# 03-multimodal-battery-charger.net
KiCad netlist of a schematic drawn in Altium Designer
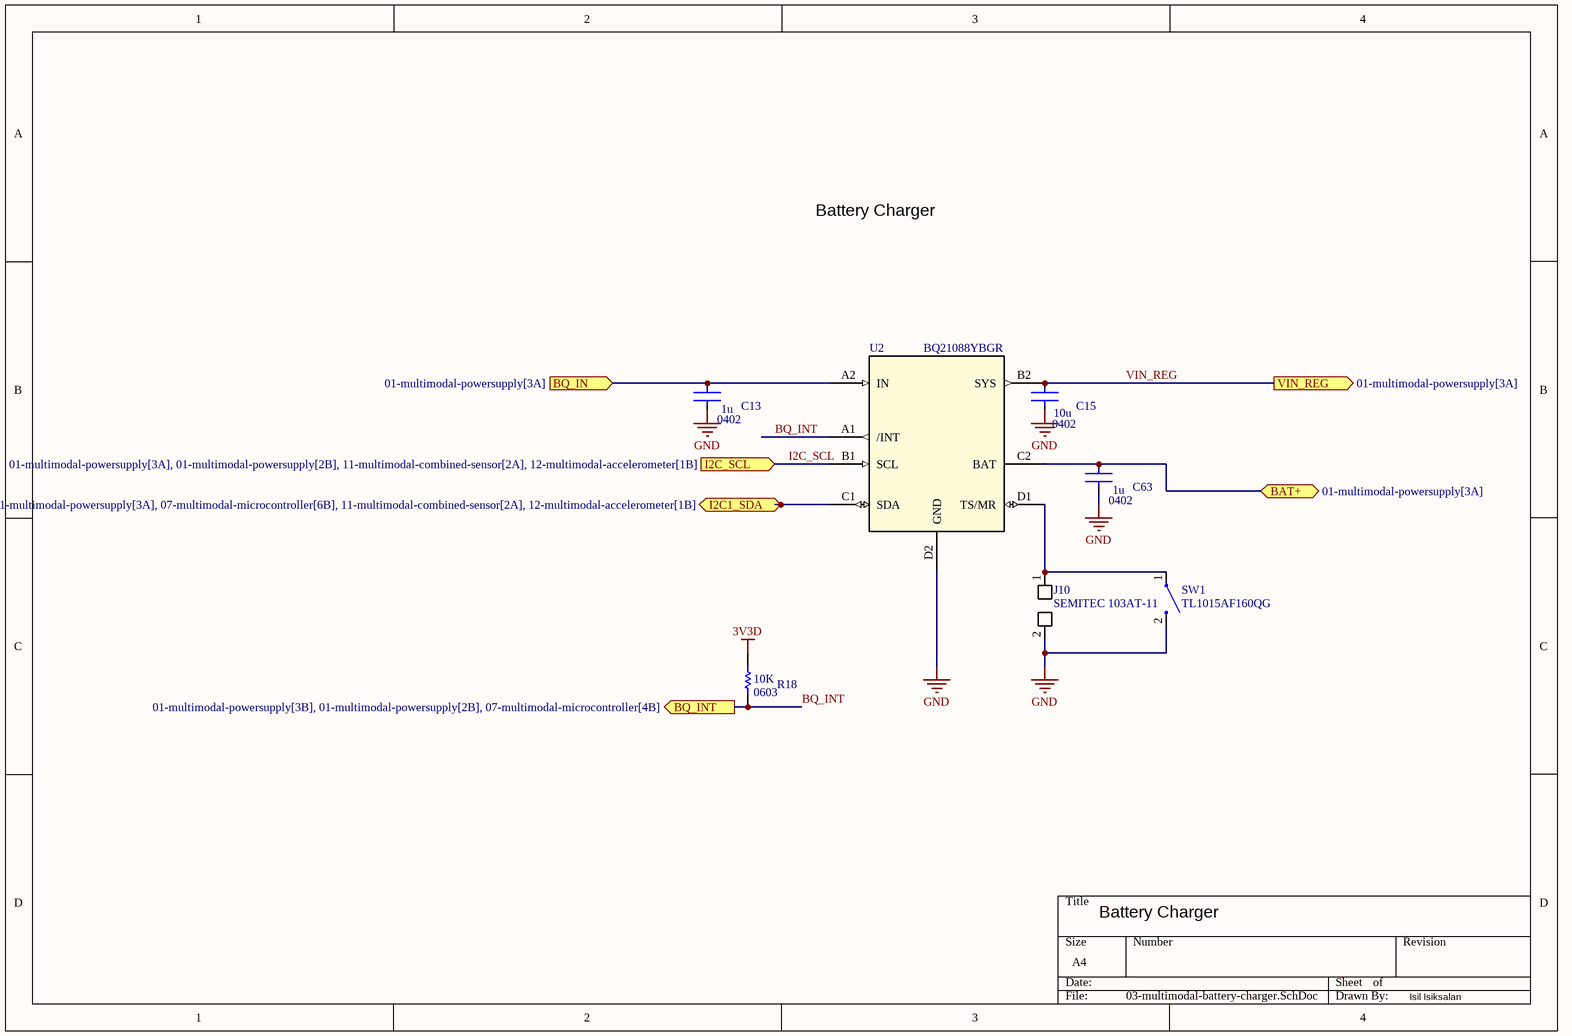
[diagram p0: 03-multimodal-battery-charger.SchDoc]

(export (version "E")
  (design (tool "Eeschema 10.0.6"))
  (components
    (comp (ref "C13")
      (value "C1005X5R1V105K050BC")
      (footprint "CAPTDK0402")
      (description "CAP CER 1UF 35V X5R 0402")
      (libsource (lib "multimodal") (part "C1005X5R1V105K050BC"))
    )
    (comp (ref "C15")
      (value "GRM155R61A106ME11D")
      (footprint "CAPTDK0402")
      (description "CAP CER 10UF 10V X5R 0402")
      (libsource (lib "multimodal") (part "GRM155R61A106ME11D"))
    )
    (comp (ref "C63")
      (value "C1005X5R1V105K050BC")
      (footprint "CAPTDK0402")
      (description "CAP CER 1UF 35V X5R 0402")
      (libsource (lib "multimodal") (part "C1005X5R1V105K050BC"))
    )
    (comp (ref "J10")
      (value "SEMITEC 103AT-11")
      (footprint "NTC_connection")
      (description "NTC THERMISTOR 10KOHM 1%")
      (libsource (lib "multimodal") (part "SEMITEC 103AT-11"))
    )
    (comp (ref "R18")
      (value "RMCF0603JG10K0")
      (footprint "RES-STACK-POLE-0603")
      (description "RES 10K OHM 5% 1/10W 0603")
      (libsource (lib "multimodal") (part "RMCF0603JG10K0"))
    )
    (comp (ref "SW1")
      (value "TL1015AF160QG")
      (footprint "TACTILE-SWITCH")
      (description "SWITCH TACTILE SPST-NO 0.05A 12V")
      (libsource (lib "multimodal") (part "TL1015AF160QG"))
    )
    (comp (ref "U2")
      (value "BQ21088YBGR")
      (footprint "YBG0008_TEX")
      (fields (field (name "COPYRIGHT") "Copyright (C) 2026 Ultra Librarian. All rights reserved."))
      (libsource (lib "multimodal") (part "BQ21088YBGR"))
    )
  )
  (nets
    (net (code "1") (name "/BAT+") (class "Default")
      (node (ref "C63") (pin "1") (pinfunction "1_1") (pintype "passive"))
      (node (ref "U2") (pin "C2") (pinfunction "BAT_C2") (pintype "passive"))
    )
    (net (code "2") (name "/BQ_IN") (class "Default")
      (node (ref "C13") (pin "1") (pinfunction "1_1") (pintype "passive"))
      (node (ref "U2") (pin "A2") (pinfunction "IN_A2") (pintype "input"))
    )
    (net (code "3") (name "/BQ_INT") (class "Default")
      (node (ref "R18") (pin "1") (pinfunction "1_1") (pintype "passive"))
      (node (ref "U2") (pin "A1") (pinfunction "/INT_A1") (pintype "output"))
    )
    (net (code "4") (name "/I2C1_SDA") (class "Default")
      (node (ref "U2") (pin "C1") (pinfunction "SDA_C1") (pintype "bidirectional"))
    )
    (net (code "5") (name "/I2C_SCL") (class "Default")
      (node (ref "U2") (pin "B1") (pinfunction "SCL_B1") (pintype "input"))
    )
    (net (code "6") (name "/VIN_REG") (class "Default")
      (node (ref "C15") (pin "1") (pinfunction "1_1") (pintype "passive"))
      (node (ref "U2") (pin "B2") (pinfunction "SYS_B2") (pintype "output"))
    )
    (net (code "7") (name "3V3D") (class "Default")
      (node (ref "R18") (pin "2") (pinfunction "2_2") (pintype "passive"))
    )
    (net (code "8") (name "GND") (class "Default")
      (node (ref "C13") (pin "2") (pinfunction "2_2") (pintype "passive"))
      (node (ref "C15") (pin "2") (pinfunction "2_2") (pintype "passive"))
      (node (ref "C63") (pin "2") (pinfunction "2_2") (pintype "passive"))
      (node (ref "J10") (pin "2") (pinfunction "2_2") (pintype "passive"))
      (node (ref "SW1") (pin "2") (pinfunction "2_2") (pintype "passive"))
      (node (ref "U2") (pin "D2") (pinfunction "GND_D2") (pintype "power_in"))
    )
    (net (code "9") (name "Net-(U2-TS{slash}MR)") (class "Default")
      (node (ref "J10") (pin "1") (pinfunction "1_1") (pintype "passive"))
      (node (ref "SW1") (pin "1") (pinfunction "1_1") (pintype "passive"))
      (node (ref "U2") (pin "D1") (pinfunction "TS/MR_D1") (pintype "bidirectional"))
    )
  )
)
